# Pheripherials.net
KiCad netlist of a schematic drawn in Altium Designer
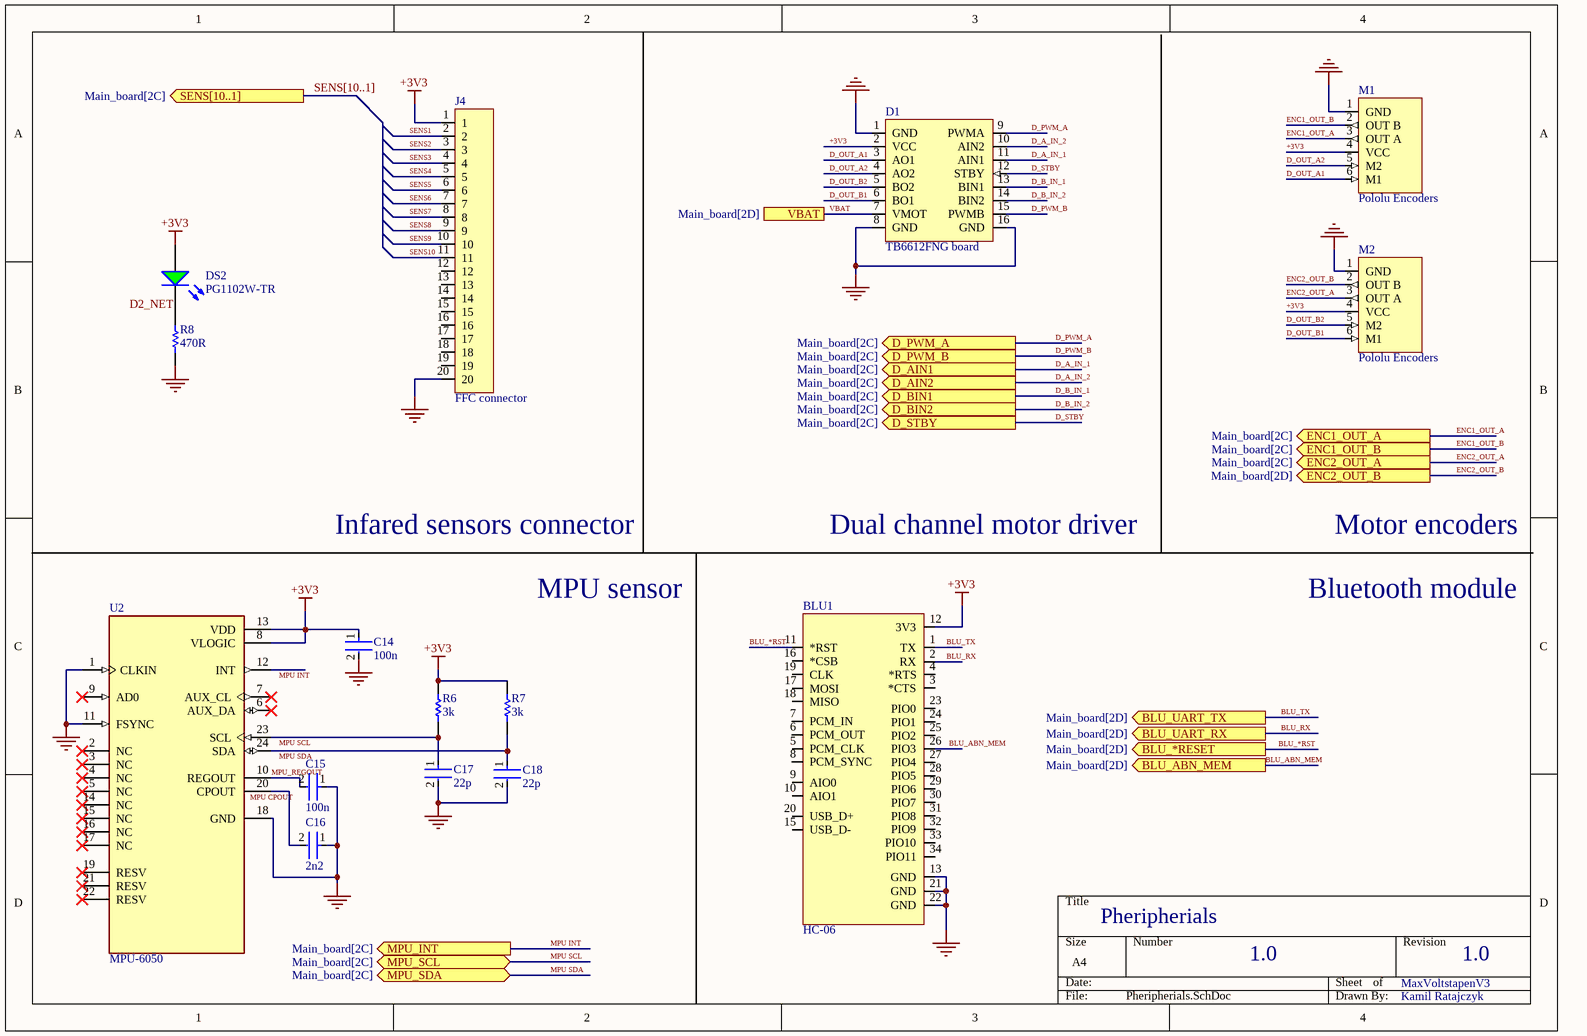
[diagram p0: Pheripherials.SchDoc]

(export (version "E")
  (design (tool "Eeschema 10.0.6"))
  (components
    (comp (ref "BLU1") (value "HC-06") (libsource (lib "Schlib1") (part "BLUETOOTH-SERIAL-HC-06")))
    (comp (ref "C14")
      (value "100n")
      (footprint "FP-CC0805-0_85-MFG")
      (description "CAP CER 0.1UF 16V X7R 0805")
      (fields
        (field (name "MANUFACTURER PART NUMBER") "CC0805KRX7R7BB104")
        (field (name "MANUFACTURER") "Yageo")
      )
      (libsource (lib "Altium Content Vault") (part "11868f565c42a9108669ba33697ecf6"))
    )
    (comp (ref "C15")
      (value "100n")
      (footprint "FP-CC0805-0_85-MFG")
      (description "CAP CER 0.1UF 16V X7R 0805")
      (fields
        (field (name "MANUFACTURER PART NUMBER") "CC0805KRX7R7BB104")
        (field (name "MANUFACTURER") "Yageo")
      )
      (libsource (lib "Altium Content Vault") (part "11868f565c42a9108669ba33697ecf6"))
    )
    (comp (ref "C16")
      (value "2n2")
      (footprint "FP-CC0805-0_85-MFG")
      (description "CAP CER 0.1UF 16V X7R 0805")
      (fields
        (field (name "MANUFACTURER PART NUMBER") "CC0805KRX7R7BB104")
        (field (name "MANUFACTURER") "Yageo")
      )
      (libsource (lib "Altium Content Vault") (part "11868f565c42a9108669ba33697ecf6"))
    )
    (comp (ref "C17")
      (value "22p")
      (footprint "FP-CC0805-0_85-MFG")
      (description "CAP CER 0.1UF 16V X7R 0805")
      (fields
        (field (name "MANUFACTURER PART NUMBER") "CC0805KRX7R7BB104")
        (field (name "MANUFACTURER") "Yageo")
      )
      (libsource (lib "Altium Content Vault") (part "11868f565c42a9108669ba33697ecf6"))
    )
    (comp (ref "C18")
      (value "22p")
      (footprint "FP-CC0805-0_85-MFG")
      (description "CAP CER 0.1UF 16V X7R 0805")
      (fields
        (field (name "MANUFACTURER PART NUMBER") "CC0805KRX7R7BB104")
        (field (name "MANUFACTURER") "Yageo")
      )
      (libsource (lib "Altium Content Vault") (part "11868f565c42a9108669ba33697ecf6"))
    )
    (comp (ref "D1")
      (value "TB6612FNG board")
      (footprint "TB6612FNG board footprint")
      (libsource (lib "Schlib1") (part "TB6612FNG board"))
    )
    (comp (ref "DS2")
      (value "PG1102W-TR")
      (footprint "STEC-1102W_V")
      (description "Green LED, 567 nm, 2.1 V, 30 mA, -30 to 85 degC, 2-Pin SMD, RoHS, Tape and Reel")
      (fields (field (name "MANUFACTURER") "Stanley Electric"))
      (libsource (lib "Altium Content Vault") (part "LED-GREEN-AK-2"))
    )
    (comp (ref "J4")
      (value "FFC connector")
      (footprint "GCT_FFC2B35-20-G_REVA2")
      (libsource (lib "Schlib1") (part "FFC2B35-20-G"))
    )
    (comp (ref "M1")
      (value "Pololu Encoders")
      (footprint "Encoders Pololu footprint")
      (libsource (lib "Schlib1") (part "Pololu Encoders"))
    )
    (comp (ref "M2")
      (value "Pololu Encoders")
      (footprint "Encoders Pololu footprint")
      (libsource (lib "Schlib1") (part "Pololu Encoders"))
    )
    (comp (ref "R6")
      (value "3k")
      (footprint "RESC2013X60X35NL10T20")
      (description "Chip Resistor, 10 KOhm, +/- 1%, 0.125 W, -55 to 155 degC, 0805 (2012 Metric), RoHS, Tape and Reel")
      (fields (field (name "MANUFACTURER") "Yageo"))
      (libsource (lib "Altium Content Vault") (part "RES-2"))
    )
    (comp (ref "R7")
      (value "3k")
      (footprint "RESC2013X60X35NL10T20")
      (description "Chip Resistor, 10 KOhm, +/- 1%, 0.125 W, -55 to 155 degC, 0805 (2012 Metric), RoHS, Tape and Reel")
      (fields (field (name "MANUFACTURER") "Yageo"))
      (libsource (lib "Altium Content Vault") (part "RES-2"))
    )
    (comp (ref "R8")
      (value "470R")
      (footprint "RESC2013X60X35NL10T20")
      (description "Chip Resistor, 10 KOhm, +/- 1%, 0.125 W, -55 to 155 degC, 0805 (2012 Metric), RoHS, Tape and Reel")
      (fields (field (name "MANUFACTURER") "Yageo"))
      (libsource (lib "Altium Content Vault") (part "RES-2"))
    )
    (comp (ref "U2")
      (value "MPU-6050")
      (footprint "QFN50P400X400X95-24N")
      (description "MPU-6050 series Accelerometer, Gyroscope, 3 Axis Sensor Evaluation Board")
      (fields (field (name "MF") "TDK InvenSense"))
      (libsource (lib "Schlib1") (part "MPU-6050"))
    )
  )
  (nets
    (net (code "1") (name "+3V3") (class "Default")
      (node (ref "BLU1") (pin "12") (pinfunction "3V3_12") (pintype "passive"))
      (node (ref "C14") (pin "1") (pinfunction "1_1") (pintype "passive"))
      (node (ref "D1") (pin "2") (pinfunction "VCC_2") (pintype "power_in"))
      (node (ref "DS2") (pin "1") (pinfunction "A_1") (pintype "passive"))
      (node (ref "J4") (pin "1") (pinfunction "1_1") (pintype "passive"))
      (node (ref "M1") (pin "4") (pinfunction "VCC_4") (pintype "power_in"))
      (node (ref "M2") (pin "4") (pinfunction "VCC_4") (pintype "power_in"))
      (node (ref "R6") (pin "1") (pinfunction "1_1") (pintype "passive"))
      (node (ref "R7") (pin "1") (pinfunction "1_1") (pintype "passive"))
      (node (ref "U2") (pin "13") (pinfunction "VDD_13") (pintype "power_in"))
      (node (ref "U2") (pin "8") (pinfunction "VLOGIC_8") (pintype "power_in"))
    )
    (net (code "2") (name "/BLU_*RST") (class "Default")
      (node (ref "BLU1") (pin "11") (pinfunction "*RST_11") (pintype "passive"))
    )
    (net (code "3") (name "/BLU_ABN_MEM") (class "Default")
      (node (ref "BLU1") (pin "26") (pinfunction "PIO3_26") (pintype "passive"))
    )
    (net (code "4") (name "/BLU_RX") (class "Default")
      (node (ref "BLU1") (pin "2") (pinfunction "RX_2") (pintype "passive"))
    )
    (net (code "5") (name "/BLU_TX") (class "Default")
      (node (ref "BLU1") (pin "1") (pinfunction "TX_1") (pintype "passive"))
    )
    (net (code "6") (name "/D2_NET") (class "Default")
      (node (ref "DS2") (pin "2") (pinfunction "K_2") (pintype "passive"))
      (node (ref "R8") (pin "1") (pinfunction "1_1") (pintype "passive"))
    )
    (net (code "7") (name "/D_A_IN_1") (class "Default")
      (node (ref "D1") (pin "11") (pinfunction "AIN1_11") (pintype "passive"))
    )
    (net (code "8") (name "/D_A_IN_2") (class "Default")
      (node (ref "D1") (pin "10") (pinfunction "AIN2_10") (pintype "passive"))
    )
    (net (code "9") (name "/D_B_IN_1") (class "Default")
      (node (ref "D1") (pin "13") (pinfunction "BIN1_13") (pintype "passive"))
    )
    (net (code "10") (name "/D_B_IN_2") (class "Default")
      (node (ref "D1") (pin "14") (pinfunction "BIN2_14") (pintype "passive"))
    )
    (net (code "11") (name "/D_OUT_A1") (class "Default")
      (node (ref "D1") (pin "3") (pinfunction "AO1_3") (pintype "bidirectional"))
      (node (ref "M1") (pin "6") (pinfunction "M1_6") (pintype "input"))
    )
    (net (code "12") (name "/D_OUT_A2") (class "Default")
      (node (ref "D1") (pin "4") (pinfunction "AO2_4") (pintype "bidirectional"))
      (node (ref "M1") (pin "5") (pinfunction "M2_5") (pintype "input"))
    )
    (net (code "13") (name "/D_OUT_B1") (class "Default")
      (node (ref "D1") (pin "6") (pinfunction "BO1_6") (pintype "bidirectional"))
      (node (ref "M2") (pin "6") (pinfunction "M1_6") (pintype "input"))
    )
    (net (code "14") (name "/D_OUT_B2") (class "Default")
      (node (ref "D1") (pin "5") (pinfunction "BO2_5") (pintype "bidirectional"))
      (node (ref "M2") (pin "5") (pinfunction "M2_5") (pintype "input"))
    )
    (net (code "15") (name "/D_PWM_A") (class "Default")
      (node (ref "D1") (pin "9") (pinfunction "PWMA_9") (pintype "passive"))
    )
    (net (code "16") (name "/D_PWM_B") (class "Default")
      (node (ref "D1") (pin "15") (pinfunction "PWMB_15") (pintype "passive"))
    )
    (net (code "17") (name "/D_STBY") (class "Default")
      (node (ref "D1") (pin "12") (pinfunction "STBY_12") (pintype "input"))
    )
    (net (code "18") (name "/ENC1_OUT_A") (class "Default")
      (node (ref "M1") (pin "3") (pinfunction "OUT_A_3") (pintype "output"))
    )
    (net (code "19") (name "/ENC1_OUT_B") (class "Default")
      (node (ref "M1") (pin "2") (pinfunction "OUT_B_2") (pintype "output"))
    )
    (net (code "20") (name "/ENC2_OUT_A") (class "Default")
      (node (ref "M2") (pin "3") (pinfunction "OUT_A_3") (pintype "output"))
    )
    (net (code "21") (name "/ENC2_OUT_B") (class "Default")
      (node (ref "M2") (pin "2") (pinfunction "OUT_B_2") (pintype "output"))
    )
    (net (code "23") (name "/MPU INT") (class "Default")
      (node (ref "U2") (pin "12") (pinfunction "INT_12") (pintype "output"))
    )
    (net (code "24") (name "/MPU SCL") (class "Default")
      (node (ref "C17") (pin "1") (pinfunction "1_1") (pintype "passive"))
      (node (ref "R6") (pin "2") (pinfunction "2_2") (pintype "passive"))
      (node (ref "U2") (pin "23") (pinfunction "SCL_23") (pintype "input"))
    )
    (net (code "25") (name "/MPU SDA") (class "Default")
      (node (ref "C18") (pin "1") (pinfunction "1_1") (pintype "passive"))
      (node (ref "R7") (pin "2") (pinfunction "2_2") (pintype "passive"))
      (node (ref "U2") (pin "24") (pinfunction "SDA_24") (pintype "bidirectional"))
    )
    (net (code "26") (name "/MPU_REGOUT") (class "Default")
      (node (ref "C15") (pin "2") (pinfunction "2_2") (pintype "passive"))
      (node (ref "U2") (pin "10") (pinfunction "REGOUT_10") (pintype "passive"))
    )
    (net (code "27") (name "/SENS1") (class "Default")
      (node (ref "J4") (pin "2") (pinfunction "2_2") (pintype "passive"))
    )
    (net (code "28") (name "/SENS2") (class "Default")
      (node (ref "J4") (pin "3") (pinfunction "3_3") (pintype "passive"))
    )
    (net (code "29") (name "/SENS3") (class "Default")
      (node (ref "J4") (pin "4") (pinfunction "4_4") (pintype "passive"))
    )
    (net (code "30") (name "/SENS4") (class "Default")
      (node (ref "J4") (pin "5") (pinfunction "5_5") (pintype "passive"))
    )
    (net (code "31") (name "/SENS5") (class "Default")
      (node (ref "J4") (pin "6") (pinfunction "6_6") (pintype "passive"))
    )
    (net (code "32") (name "/SENS6") (class "Default")
      (node (ref "J4") (pin "7") (pinfunction "7_7") (pintype "passive"))
    )
    (net (code "33") (name "/SENS7") (class "Default")
      (node (ref "J4") (pin "8") (pinfunction "8_8") (pintype "passive"))
    )
    (net (code "34") (name "/SENS8") (class "Default")
      (node (ref "J4") (pin "9") (pinfunction "9_9") (pintype "passive"))
    )
    (net (code "35") (name "/SENS9") (class "Default")
      (node (ref "J4") (pin "10") (pinfunction "10_10") (pintype "passive"))
    )
    (net (code "36") (name "/SENS10") (class "Default")
      (node (ref "J4") (pin "11") (pinfunction "11_11") (pintype "passive"))
    )
    (net (code "38") (name "/VBAT") (class "Default")
      (node (ref "D1") (pin "7") (pinfunction "VMOT_7") (pintype "power_in"))
    )
    (net (code "39") (name "GND") (class "Default")
      (node (ref "BLU1") (pin "13") (pinfunction "GND_13") (pintype "passive"))
      (node (ref "BLU1") (pin "21") (pinfunction "GND_21") (pintype "passive"))
      (node (ref "BLU1") (pin "22") (pinfunction "GND_22") (pintype "passive"))
      (node (ref "C14") (pin "2") (pinfunction "2_2") (pintype "passive"))
      (node (ref "C15") (pin "1") (pinfunction "1_1") (pintype "passive"))
      (node (ref "C16") (pin "1") (pinfunction "1_1") (pintype "passive"))
      (node (ref "C17") (pin "2") (pinfunction "2_2") (pintype "passive"))
      (node (ref "C18") (pin "2") (pinfunction "2_2") (pintype "passive"))
      (node (ref "D1") (pin "1") (pinfunction "GND_1") (pintype "power_in"))
      (node (ref "D1") (pin "16") (pinfunction "GND_16") (pintype "power_in"))
      (node (ref "D1") (pin "8") (pinfunction "GND_8") (pintype "power_in"))
      (node (ref "J4") (pin "20") (pinfunction "20_20") (pintype "passive"))
      (node (ref "M1") (pin "1") (pinfunction "GND_1") (pintype "power_in"))
      (node (ref "M2") (pin "1") (pinfunction "GND_1") (pintype "power_in"))
      (node (ref "R8") (pin "2") (pinfunction "2_2") (pintype "passive"))
      (node (ref "U2") (pin "1") (pinfunction "CLKIN_1") (pintype "input"))
      (node (ref "U2") (pin "11") (pinfunction "FSYNC_11") (pintype "input"))
      (node (ref "U2") (pin "18") (pinfunction "GND_18") (pintype "power_in"))
    )
    (net (code "40") (name "Net-(U2-CPOUT)") (class "Default")
      (node (ref "C16") (pin "2") (pinfunction "2_2") (pintype "passive"))
      (node (ref "U2") (pin "20") (pinfunction "CPOUT_20") (pintype "passive"))
    )
    (net (code "41") (name "unconnected-(BLU1-*CSB-Pad16)") (class "Default")
      (node (ref "BLU1") (pin "16") (pinfunction "*CSB_16") (pintype "passive"))
    )
    (net (code "42") (name "unconnected-(BLU1-*CTS-Pad3)") (class "Default")
      (node (ref "BLU1") (pin "3") (pinfunction "*CTS_3") (pintype "passive"))
    )
    (net (code "43") (name "unconnected-(BLU1-*RTS-Pad4)") (class "Default")
      (node (ref "BLU1") (pin "4") (pinfunction "*RTS_4") (pintype "passive"))
    )
    (net (code "44") (name "unconnected-(BLU1-AIO0-Pad9)") (class "Default")
      (node (ref "BLU1") (pin "9") (pinfunction "AIO0_9") (pintype "passive"))
    )
    (net (code "45") (name "unconnected-(BLU1-AIO1-Pad10)") (class "Default")
      (node (ref "BLU1") (pin "10") (pinfunction "AIO1_10") (pintype "passive"))
    )
    (net (code "46") (name "unconnected-(BLU1-CLK-Pad19)") (class "Default")
      (node (ref "BLU1") (pin "19") (pinfunction "CLK_19") (pintype "passive"))
    )
    (net (code "47") (name "unconnected-(BLU1-MISO-Pad18)") (class "Default")
      (node (ref "BLU1") (pin "18") (pinfunction "MISO_18") (pintype "passive"))
    )
    (net (code "48") (name "unconnected-(BLU1-MOSI-Pad17)") (class "Default")
      (node (ref "BLU1") (pin "17") (pinfunction "MOSI_17") (pintype "passive"))
    )
    (net (code "49") (name "unconnected-(BLU1-PCM_CLK-Pad5)") (class "Default")
      (node (ref "BLU1") (pin "5") (pinfunction "PCM_CLK_5") (pintype "passive"))
    )
    (net (code "50") (name "unconnected-(BLU1-PCM_IN-Pad7)") (class "Default")
      (node (ref "BLU1") (pin "7") (pinfunction "PCM_IN_7") (pintype "passive"))
    )
    (net (code "51") (name "unconnected-(BLU1-PCM_OUT-Pad6)") (class "Default")
      (node (ref "BLU1") (pin "6") (pinfunction "PCM_OUT_6") (pintype "passive"))
    )
    (net (code "52") (name "unconnected-(BLU1-PCM_SYNC-Pad8)") (class "Default")
      (node (ref "BLU1") (pin "8") (pinfunction "PCM_SYNC_8") (pintype "passive"))
    )
    (net (code "53") (name "unconnected-(BLU1-PIO0-Pad23)") (class "Default")
      (node (ref "BLU1") (pin "23") (pinfunction "PIO0_23") (pintype "passive"))
    )
    (net (code "54") (name "unconnected-(BLU1-PIO1-Pad24)") (class "Default")
      (node (ref "BLU1") (pin "24") (pinfunction "PIO1_24") (pintype "passive"))
    )
    (net (code "55") (name "unconnected-(BLU1-PIO2-Pad25)") (class "Default")
      (node (ref "BLU1") (pin "25") (pinfunction "PIO2_25") (pintype "passive"))
    )
    (net (code "56") (name "unconnected-(BLU1-PIO4-Pad27)") (class "Default")
      (node (ref "BLU1") (pin "27") (pinfunction "PIO4_27") (pintype "passive"))
    )
    (net (code "57") (name "unconnected-(BLU1-PIO5-Pad28)") (class "Default")
      (node (ref "BLU1") (pin "28") (pinfunction "PIO5_28") (pintype "passive"))
    )
    (net (code "58") (name "unconnected-(BLU1-PIO6-Pad29)") (class "Default")
      (node (ref "BLU1") (pin "29") (pinfunction "PIO6_29") (pintype "passive"))
    )
    (net (code "59") (name "unconnected-(BLU1-PIO7-Pad30)") (class "Default")
      (node (ref "BLU1") (pin "30") (pinfunction "PIO7_30") (pintype "passive"))
    )
    (net (code "60") (name "unconnected-(BLU1-PIO8-Pad31)") (class "Default")
      (node (ref "BLU1") (pin "31") (pinfunction "PIO8_31") (pintype "passive"))
    )
    (net (code "61") (name "unconnected-(BLU1-PIO9-Pad32)") (class "Default")
      (node (ref "BLU1") (pin "32") (pinfunction "PIO9_32") (pintype "passive"))
    )
    (net (code "62") (name "unconnected-(BLU1-PIO10-Pad33)") (class "Default")
      (node (ref "BLU1") (pin "33") (pinfunction "PIO10_33") (pintype "passive"))
    )
    (net (code "63") (name "unconnected-(BLU1-PIO11-Pad34)") (class "Default")
      (node (ref "BLU1") (pin "34") (pinfunction "PIO11_34") (pintype "passive"))
    )
    (net (code "64") (name "unconnected-(BLU1-USB_D+-Pad20)") (class "Default")
      (node (ref "BLU1") (pin "20") (pinfunction "USB_D+_20") (pintype "passive"))
    )
    (net (code "65") (name "unconnected-(BLU1-USB_D--Pad15)") (class "Default")
      (node (ref "BLU1") (pin "15") (pinfunction "USB_D-_15") (pintype "passive"))
    )
    (net (code "66") (name "unconnected-(J4-Pad12)") (class "Default")
      (node (ref "J4") (pin "12") (pinfunction "12_12") (pintype "passive"))
    )
    (net (code "67") (name "unconnected-(J4-Pad13)") (class "Default")
      (node (ref "J4") (pin "13") (pinfunction "13_13") (pintype "passive"))
    )
    (net (code "68") (name "unconnected-(J4-Pad14)") (class "Default")
      (node (ref "J4") (pin "14") (pinfunction "14_14") (pintype "passive"))
    )
    (net (code "69") (name "unconnected-(J4-Pad15)") (class "Default")
      (node (ref "J4") (pin "15") (pinfunction "15_15") (pintype "passive"))
    )
    (net (code "70") (name "unconnected-(J4-Pad16)") (class "Default")
      (node (ref "J4") (pin "16") (pinfunction "16_16") (pintype "passive"))
    )
    (net (code "71") (name "unconnected-(J4-Pad17)") (class "Default")
      (node (ref "J4") (pin "17") (pinfunction "17_17") (pintype "passive"))
    )
    (net (code "72") (name "unconnected-(J4-Pad18)") (class "Default")
      (node (ref "J4") (pin "18") (pinfunction "18_18") (pintype "passive"))
    )
    (net (code "73") (name "unconnected-(J4-Pad19)") (class "Default")
      (node (ref "J4") (pin "19") (pinfunction "19_19") (pintype "passive"))
    )
    (net (code "74") (name "unconnected-(U2-AD0-Pad9)") (class "Default")
      (node (ref "U2") (pin "9") (pinfunction "AD0_9") (pintype "input+no_connect"))
    )
    (net (code "75") (name "unconnected-(U2-AUX_CL-Pad7)") (class "Default")
      (node (ref "U2") (pin "7") (pinfunction "AUX_CL_7") (pintype "output+no_connect"))
    )
    (net (code "76") (name "unconnected-(U2-AUX_DA-Pad6)") (class "Default")
      (node (ref "U2") (pin "6") (pinfunction "AUX_DA_6") (pintype "bidirectional+no_connect"))
    )
    (net (code "77") (name "unconnected-(U2-NC-Pad2)") (class "Default")
      (node (ref "U2") (pin "2") (pinfunction "NC_2") (pintype "passive+no_connect"))
    )
    (net (code "78") (name "unconnected-(U2-NC-Pad3)") (class "Default")
      (node (ref "U2") (pin "3") (pinfunction "NC_3") (pintype "passive+no_connect"))
    )
    (net (code "79") (name "unconnected-(U2-NC-Pad4)") (class "Default")
      (node (ref "U2") (pin "4") (pinfunction "NC_4") (pintype "passive+no_connect"))
    )
    (net (code "80") (name "unconnected-(U2-NC-Pad5)") (class "Default")
      (node (ref "U2") (pin "5") (pinfunction "NC_5") (pintype "passive+no_connect"))
    )
    (net (code "81") (name "unconnected-(U2-NC-Pad14)") (class "Default")
      (node (ref "U2") (pin "14") (pinfunction "NC_14") (pintype "passive+no_connect"))
    )
    (net (code "82") (name "unconnected-(U2-NC-Pad15)") (class "Default")
      (node (ref "U2") (pin "15") (pinfunction "NC_15") (pintype "passive+no_connect"))
    )
    (net (code "83") (name "unconnected-(U2-NC-Pad16)") (class "Default")
      (node (ref "U2") (pin "16") (pinfunction "NC_16") (pintype "passive+no_connect"))
    )
    (net (code "84") (name "unconnected-(U2-NC-Pad17)") (class "Default")
      (node (ref "U2") (pin "17") (pinfunction "NC_17") (pintype "passive+no_connect"))
    )
    (net (code "85") (name "unconnected-(U2-RESV-Pad19)") (class "Default")
      (node (ref "U2") (pin "19") (pinfunction "RESV_19") (pintype "passive+no_connect"))
    )
    (net (code "86") (name "unconnected-(U2-RESV-Pad21)") (class "Default")
      (node (ref "U2") (pin "21") (pinfunction "RESV_21") (pintype "passive+no_connect"))
    )
    (net (code "87") (name "unconnected-(U2-RESV-Pad22)") (class "Default")
      (node (ref "U2") (pin "22") (pinfunction "RESV_22") (pintype "passive+no_connect"))
    )
  )
)
